# LIFT_DRIVER.net
KiCad netlist of a schematic drawn in Altium Designer
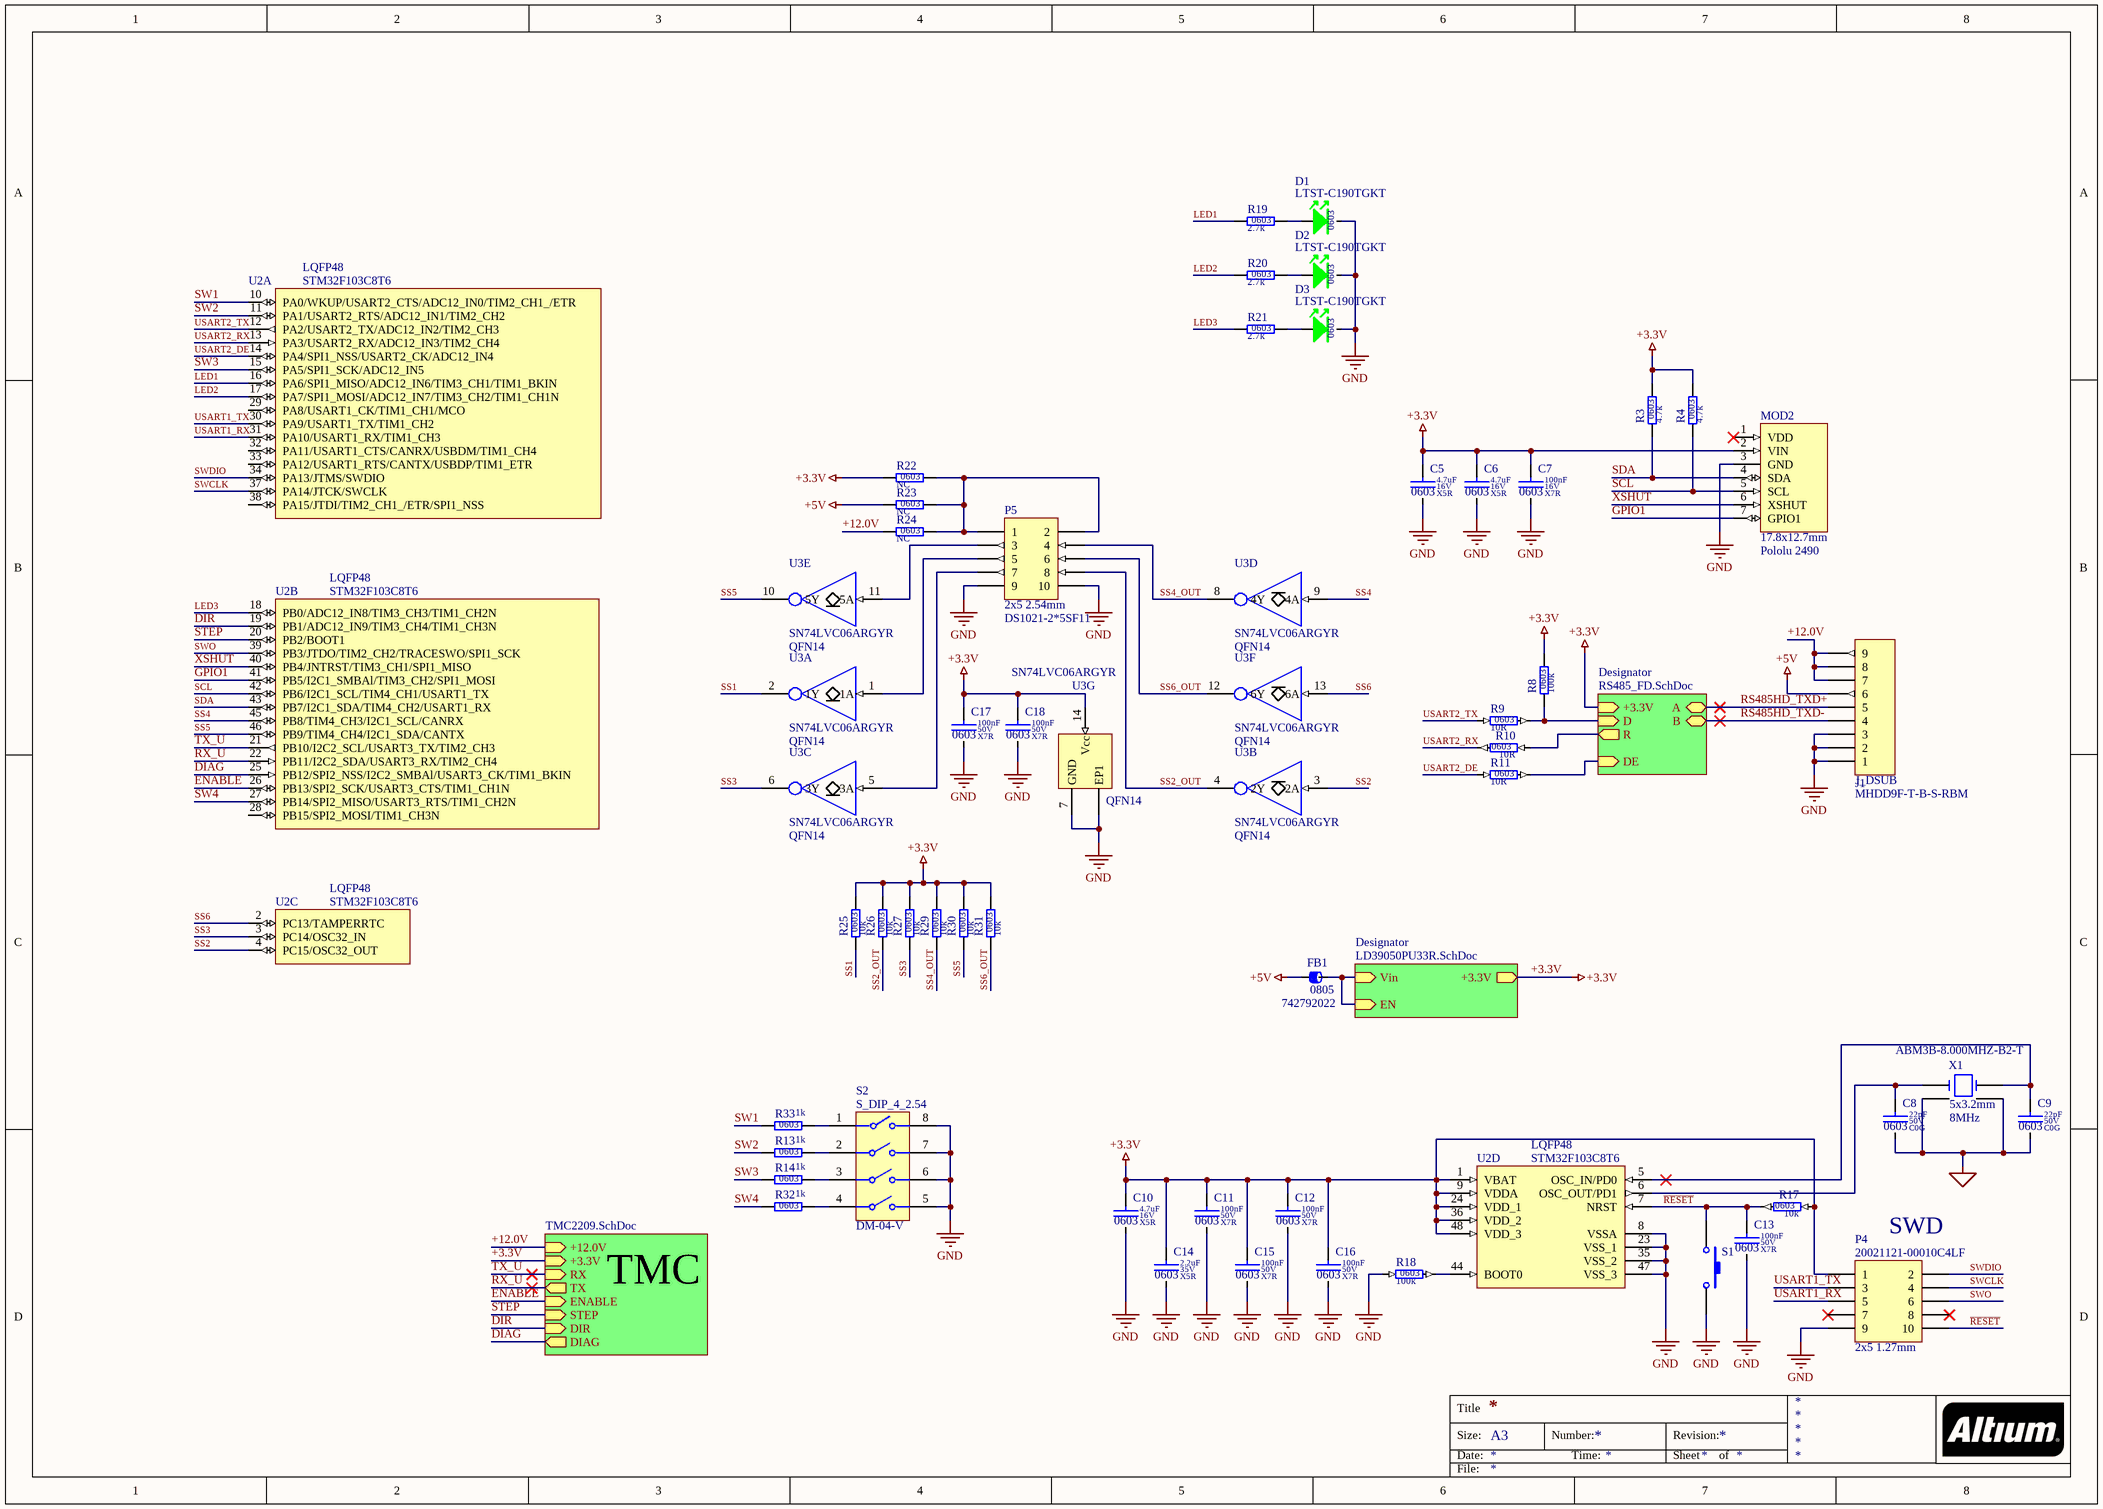
[diagram p0: LIFT_DRIVER.SchDoc]

(export (version "E")
  (design (tool "Eeschema 10.0.6"))
  (components
    (comp (ref "C5")
      (value "4.7uF")
      (footprint "C_0603_1608")
      (description "Capacitor")
      (fields
        (field (name "DIELECTRIC") "X5R")
        (field (name "VOLTAGE") "16V")
        (field (name "SCH_FOOTPRINT") "0603")
        (field (name "PART NUMBER") "C_4.7uF_16V_X5R_0603_10")
        (field (name "MANUFACTURER") "Murata")
      )
      (libsource (lib "Library") (part "C"))
    )
    (comp (ref "C6")
      (value "4.7uF")
      (footprint "C_0603_1608")
      (description "Capacitor")
      (fields
        (field (name "DIELECTRIC") "X5R")
        (field (name "VOLTAGE") "16V")
        (field (name "SCH_FOOTPRINT") "0603")
        (field (name "PART NUMBER") "C_4.7uF_16V_X5R_0603_10")
        (field (name "MANUFACTURER") "Murata")
      )
      (libsource (lib "Library") (part "C"))
    )
    (comp (ref "C7")
      (value "100nF")
      (footprint "C_0603_1608")
      (description "Capacitor")
      (fields
        (field (name "DIELECTRIC") "X7R")
        (field (name "VOLTAGE") "16V")
        (field (name "SCH_FOOTPRINT") "0603")
        (field (name "PART NUMBER") "C_100nF_16V_X7R_0603_10")
        (field (name "MANUFACTURER") "Kemet")
      )
      (libsource (lib "Library") (part "C"))
    )
    (comp (ref "C8")
      (value "22pF")
      (footprint "C_0603_1608")
      (description "Capacitor")
      (fields
        (field (name "DIELECTRIC") "C0G")
        (field (name "VOLTAGE") "50V")
        (field (name "SCH_FOOTPRINT") "0603")
        (field (name "PART NUMBER") "C_22pF_50V_C0G_0603_5")
        (field (name "MANUFACTURER") "AVX")
      )
      (libsource (lib "Library") (part "C"))
    )
    (comp (ref "C9")
      (value "22pF")
      (footprint "C_0603_1608")
      (description "Capacitor")
      (fields
        (field (name "DIELECTRIC") "C0G")
        (field (name "VOLTAGE") "50V")
        (field (name "SCH_FOOTPRINT") "0603")
        (field (name "PART NUMBER") "C_22pF_50V_C0G_0603_5")
        (field (name "MANUFACTURER") "AVX")
      )
      (libsource (lib "Library") (part "C"))
    )
    (comp (ref "C10")
      (value "4.7uF")
      (footprint "C_0603_1608")
      (description "Capacitor")
      (fields
        (field (name "DIELECTRIC") "X5R")
        (field (name "VOLTAGE") "16V")
        (field (name "SCH_FOOTPRINT") "0603")
        (field (name "PART NUMBER") "C_4.7uF_16V_X5R_0603_10")
        (field (name "MANUFACTURER") "Murata")
      )
      (libsource (lib "Library") (part "C"))
    )
    (comp (ref "C11")
      (value "100nF")
      (footprint "C_0603_1608")
      (description "Capacitor")
      (fields
        (field (name "DIELECTRIC") "X7R")
        (field (name "VOLTAGE") "50V")
        (field (name "SCH_FOOTPRINT") "0603")
        (field (name "PART NUMBER") "C_100nF_50V_X7R_0603_5")
        (field (name "MANUFACTURER") "Samsung")
      )
      (libsource (lib "Library") (part "C"))
    )
    (comp (ref "C12")
      (value "100nF")
      (footprint "C_0603_1608")
      (description "Capacitor")
      (fields
        (field (name "DIELECTRIC") "X7R")
        (field (name "VOLTAGE") "50V")
        (field (name "SCH_FOOTPRINT") "0603")
        (field (name "PART NUMBER") "C_100nF_50V_X7R_0603_5")
        (field (name "MANUFACTURER") "Samsung")
      )
      (libsource (lib "Library") (part "C"))
    )
    (comp (ref "C13")
      (value "100nF")
      (footprint "C_0603_1608")
      (description "Capacitor")
      (fields
        (field (name "DIELECTRIC") "X7R")
        (field (name "VOLTAGE") "50V")
        (field (name "SCH_FOOTPRINT") "0603")
        (field (name "PART NUMBER") "C_100nF_50V_X7R_0603_5")
        (field (name "MANUFACTURER") "Samsung")
      )
      (libsource (lib "Library") (part "C"))
    )
    (comp (ref "C14")
      (value "2.2uF")
      (footprint "C_0603_1608")
      (description "Capacitor")
      (fields
        (field (name "DIELECTRIC") "X5R")
        (field (name "VOLTAGE") "35V")
        (field (name "SCH_FOOTPRINT") "0603")
        (field (name "PART NUMBER") "C_2.2uF_35V_X5R_0603_10")
        (field (name "MANUFACTURER") "Murata")
      )
      (libsource (lib "Library") (part "C"))
    )
    (comp (ref "C15")
      (value "100nF")
      (footprint "C_0603_1608")
      (description "Capacitor")
      (fields
        (field (name "DIELECTRIC") "X7R")
        (field (name "VOLTAGE") "50V")
        (field (name "SCH_FOOTPRINT") "0603")
        (field (name "PART NUMBER") "C_100nF_50V_X7R_0603_5")
        (field (name "MANUFACTURER") "Samsung")
      )
      (libsource (lib "Library") (part "C"))
    )
    (comp (ref "C16")
      (value "100nF")
      (footprint "C_0603_1608")
      (description "Capacitor")
      (fields
        (field (name "DIELECTRIC") "X7R")
        (field (name "VOLTAGE") "50V")
        (field (name "SCH_FOOTPRINT") "0603")
        (field (name "PART NUMBER") "C_100nF_50V_X7R_0603_5")
        (field (name "MANUFACTURER") "Samsung")
      )
      (libsource (lib "Library") (part "C"))
    )
    (comp (ref "C17")
      (value "100nF")
      (footprint "C_0603_1608")
      (description "Capacitor")
      (fields
        (field (name "DIELECTRIC") "X7R")
        (field (name "VOLTAGE") "50V")
        (field (name "SCH_FOOTPRINT") "0603")
        (field (name "PART NUMBER") "C_100nF_50V_X7R_0603_5")
        (field (name "MANUFACTURER") "Samsung")
      )
      (libsource (lib "Library") (part "C"))
    )
    (comp (ref "C18")
      (value "100nF")
      (footprint "C_0603_1608")
      (description "Capacitor")
      (fields
        (field (name "DIELECTRIC") "X7R")
        (field (name "VOLTAGE") "50V")
        (field (name "SCH_FOOTPRINT") "0603")
        (field (name "PART NUMBER") "C_100nF_50V_X7R_0603_5")
        (field (name "MANUFACTURER") "Samsung")
      )
      (libsource (lib "Library") (part "C"))
    )
    (comp (ref "D1")
      (value "LTST-C190TGKT")
      (footprint "OL_0603_1608")
      (description "LED GREEN")
      (fields
        (field (name "SCH_FOOTPRINT") "0603")
        (field (name "PART NUMBER") "OL_G_0603")
        (field (name "MANUFACTURER") "Lite-On")
      )
      (libsource (lib "Library") (part "OL_G"))
    )
    (comp (ref "D2")
      (value "LTST-C190TGKT")
      (footprint "OL_0603_1608")
      (description "LED GREEN")
      (fields
        (field (name "SCH_FOOTPRINT") "0603")
        (field (name "PART NUMBER") "OL_G_0603")
        (field (name "MANUFACTURER") "Lite-On")
      )
      (libsource (lib "Library") (part "OL_G"))
    )
    (comp (ref "D3")
      (value "LTST-C190TGKT")
      (footprint "OL_0603_1608")
      (description "LED GREEN")
      (fields
        (field (name "SCH_FOOTPRINT") "0603")
        (field (name "PART NUMBER") "OL_G_0603")
        (field (name "MANUFACTURER") "Lite-On")
      )
      (libsource (lib "Library") (part "OL_G"))
    )
    (comp (ref "FB1")
      (value "742792022")
      (footprint "FB_0805_2012")
      (description "Ferrite Bead")
      (fields
        (field (name "PART NUMBER") "FB_742792022")
        (field (name "SCH_FOOTPRINT") "0805")
        (field (name "MANUFACTURER") "Wurth")
      )
      (libsource (lib "Library") (part "FB"))
    )
    (comp (ref "J1")
      (value "MHDD9F-T-B-S-RBM")
      (footprint "J_DSUB_MHDD9F-T-B-S-RBM")
      (description "Header, 9-Pin")
      (fields
        (field (name "SCH_FOOTPRINT") "J_DSUB")
        (field (name "PART NUMBER") "J_DSUB")
        (field (name "Comment") "DSUB 9 Pin")
      )
      (libsource (lib "Library") (part "J_DSUB"))
    )
    (comp (ref "MOD2")
      (value "Pololu 2490")
      (footprint "MOD_VL53L0X")
      (description "Pin Header")
      (fields
        (field (name "SCH_FOOTPRINT") "17.8x12.7mm")
        (field (name "PART NUMBER") "MOD_VL53L0X")
        (field (name "MANUFACTURER") "Polulu")
      )
      (libsource (lib "Library") (part "MOD_VL53L0X"))
    )
    (comp (ref "P4")
      (value "20021121-00010C4LF")
      (footprint "P_HEADER_2x5_1.27")
      (description "Header, 10-Pin, Dual row")
      (fields
        (field (name "PART NUMBER") "P_HEADER_2x5_1.27")
        (field (name "SCH_FOOTPRINT") "2x5 1.27mm")
        (field (name "MANUFACTURER") "FCI")
      )
      (libsource (lib "Library") (part "P_HEADER_2x5"))
    )
    (comp (ref "P5")
      (value "DS1021-2*5SF11")
      (footprint "P_HEADER_2x5_2.54")
      (description "Pin Header")
      (fields
        (field (name "SCH_FOOTPRINT") "2x5 2.54mm")
        (field (name "PART NUMBER") "P_HEADER_2x5_2.54")
        (field (name "MANUFACTURER") "Connfly")
      )
      (libsource (lib "") (part "P_HEADER_2x5_1"))
    )
    (comp (ref "R3")
      (value "4.7k")
      (footprint "R_0603_1608")
      (fields
        (field (name "SCH_FOOTPRINT") "0603")
        (field (name "PART NUMBER") "R_4.7k_0603_1")
        (field (name "VOLTAGE") "75V")
        (field (name "POWER") "100mW")
      )
      (libsource (lib "Library") (part "R"))
    )
    (comp (ref "R4")
      (value "4.7k")
      (footprint "R_0603_1608")
      (fields
        (field (name "SCH_FOOTPRINT") "0603")
        (field (name "PART NUMBER") "R_4.7k_0603_1")
        (field (name "VOLTAGE") "75V")
        (field (name "POWER") "100mW")
      )
      (libsource (lib "Library") (part "R"))
    )
    (comp (ref "R8")
      (value "100k")
      (footprint "R_0603_1608")
      (fields
        (field (name "SCH_FOOTPRINT") "0603")
        (field (name "PART NUMBER") "R_100k_0603_1")
        (field (name "VOLTAGE") "50V")
        (field (name "POWER") "100mW")
      )
      (libsource (lib "Library") (part "R"))
    )
    (comp (ref "R9")
      (value "10R")
      (footprint "R_0603_1608")
      (fields
        (field (name "SCH_FOOTPRINT") "0603")
        (field (name "PART NUMBER") "R_10R_0603_1")
        (field (name "VOLTAGE") "50V")
        (field (name "POWER") "100mW")
      )
      (libsource (lib "") (part "R_1"))
    )
    (comp (ref "R10")
      (value "10R")
      (footprint "R_0603_1608")
      (fields
        (field (name "SCH_FOOTPRINT") "0603")
        (field (name "PART NUMBER") "R_10R_0603_1")
        (field (name "VOLTAGE") "50V")
        (field (name "POWER") "100mW")
      )
      (libsource (lib "") (part "R_1"))
    )
    (comp (ref "R11")
      (value "10R")
      (footprint "R_0603_1608")
      (fields
        (field (name "SCH_FOOTPRINT") "0603")
        (field (name "PART NUMBER") "R_10R_0603_1")
        (field (name "VOLTAGE") "50V")
        (field (name "POWER") "100mW")
      )
      (libsource (lib "") (part "R_1"))
    )
    (comp (ref "R13")
      (value "1k")
      (footprint "R_0603_1608")
      (fields
        (field (name "SCH_FOOTPRINT") "0603")
        (field (name "PART NUMBER") "R_1k_0603_1")
        (field (name "VOLTAGE") "75V")
        (field (name "POWER") "100mW")
      )
      (libsource (lib "Library") (part "R"))
    )
    (comp (ref "R14")
      (value "1k")
      (footprint "R_0603_1608")
      (fields
        (field (name "SCH_FOOTPRINT") "0603")
        (field (name "PART NUMBER") "R_1k_0603_1")
        (field (name "VOLTAGE") "75V")
        (field (name "POWER") "100mW")
      )
      (libsource (lib "Library") (part "R"))
    )
    (comp (ref "R17")
      (value "10k")
      (footprint "R_0603_1608")
      (fields
        (field (name "SCH_FOOTPRINT") "0603")
        (field (name "PART NUMBER") "R_10k_0603_1")
        (field (name "VOLTAGE") "75V")
        (field (name "POWER") "100mW")
      )
      (libsource (lib "") (part "R_1"))
    )
    (comp (ref "R18")
      (value "100k")
      (footprint "R_0603_1608")
      (fields
        (field (name "SCH_FOOTPRINT") "0603")
        (field (name "PART NUMBER") "R_100k_0603_1")
        (field (name "VOLTAGE") "50V")
        (field (name "POWER") "100mW")
      )
      (libsource (lib "") (part "R_1"))
    )
    (comp (ref "R19")
      (value "2.7k")
      (footprint "R_0603_1608")
      (fields
        (field (name "SCH_FOOTPRINT") "0603")
        (field (name "PART NUMBER") "R_2.7k_0603_1")
        (field (name "VOLTAGE") "50V")
        (field (name "POWER") "100mW")
      )
      (libsource (lib "Library") (part "R"))
    )
    (comp (ref "R20")
      (value "2.7k")
      (footprint "R_0603_1608")
      (fields
        (field (name "SCH_FOOTPRINT") "0603")
        (field (name "PART NUMBER") "R_2.7k_0603_1")
        (field (name "VOLTAGE") "50V")
        (field (name "POWER") "100mW")
      )
      (libsource (lib "Library") (part "R"))
    )
    (comp (ref "R21")
      (value "2.7k")
      (footprint "R_0603_1608")
      (fields
        (field (name "SCH_FOOTPRINT") "0603")
        (field (name "PART NUMBER") "R_2.7k_0603_1")
        (field (name "VOLTAGE") "50V")
        (field (name "POWER") "100mW")
      )
      (libsource (lib "Library") (part "R"))
    )
    (comp (ref "R22")
      (value "NC")
      (footprint "R_NC_0603_1608")
      (fields
        (field (name "SCH_FOOTPRINT") "0603")
        (field (name "PART NUMBER") "R_GENERIC_0603")
        (field (name "Comment") "Resistor")
      )
      (libsource (lib "Library") (part "R"))
    )
    (comp (ref "R23")
      (value "NC")
      (footprint "R_NC_0603_1608")
      (fields
        (field (name "SCH_FOOTPRINT") "0603")
        (field (name "PART NUMBER") "R_GENERIC_0603")
        (field (name "Comment") "Resistor")
      )
      (libsource (lib "Library") (part "R"))
    )
    (comp (ref "R24")
      (value "NC")
      (footprint "R_NC_0603_1608")
      (fields
        (field (name "SCH_FOOTPRINT") "0603")
        (field (name "PART NUMBER") "R_GENERIC_0603")
        (field (name "Comment") "Resistor")
      )
      (libsource (lib "Library") (part "R"))
    )
    (comp (ref "R25")
      (value "10k")
      (footprint "R_0603_1608")
      (fields
        (field (name "SCH_FOOTPRINT") "0603")
        (field (name "PART NUMBER") "R_10k_0603_1")
        (field (name "VOLTAGE") "75V")
        (field (name "POWER") "100mW")
      )
      (libsource (lib "Library") (part "R"))
    )
    (comp (ref "R26")
      (value "10k")
      (footprint "R_0603_1608")
      (fields
        (field (name "SCH_FOOTPRINT") "0603")
        (field (name "PART NUMBER") "R_10k_0603_1")
        (field (name "VOLTAGE") "75V")
        (field (name "POWER") "100mW")
      )
      (libsource (lib "Library") (part "R"))
    )
    (comp (ref "R27")
      (value "10k")
      (footprint "R_0603_1608")
      (fields
        (field (name "SCH_FOOTPRINT") "0603")
        (field (name "PART NUMBER") "R_10k_0603_1")
        (field (name "VOLTAGE") "75V")
        (field (name "POWER") "100mW")
      )
      (libsource (lib "Library") (part "R"))
    )
    (comp (ref "R29")
      (value "10k")
      (footprint "R_0603_1608")
      (fields
        (field (name "SCH_FOOTPRINT") "0603")
        (field (name "PART NUMBER") "R_10k_0603_1")
        (field (name "VOLTAGE") "75V")
        (field (name "POWER") "100mW")
      )
      (libsource (lib "Library") (part "R"))
    )
    (comp (ref "R30")
      (value "10k")
      (footprint "R_0603_1608")
      (fields
        (field (name "SCH_FOOTPRINT") "0603")
        (field (name "PART NUMBER") "R_10k_0603_1")
        (field (name "VOLTAGE") "75V")
        (field (name "POWER") "100mW")
      )
      (libsource (lib "Library") (part "R"))
    )
    (comp (ref "R31")
      (value "10k")
      (footprint "R_0603_1608")
      (fields
        (field (name "SCH_FOOTPRINT") "0603")
        (field (name "PART NUMBER") "R_10k_0603_1")
        (field (name "VOLTAGE") "75V")
        (field (name "POWER") "100mW")
      )
      (libsource (lib "Library") (part "R"))
    )
    (comp (ref "R32")
      (value "1k")
      (footprint "R_0603_1608")
      (fields
        (field (name "SCH_FOOTPRINT") "0603")
        (field (name "PART NUMBER") "R_1k_0603_1")
        (field (name "VOLTAGE") "75V")
        (field (name "POWER") "100mW")
      )
      (libsource (lib "Library") (part "R"))
    )
    (comp (ref "R33")
      (value "1k")
      (footprint "R_0603_1608")
      (fields
        (field (name "SCH_FOOTPRINT") "0603")
        (field (name "PART NUMBER") "R_1k_0603_1")
        (field (name "VOLTAGE") "75V")
        (field (name "POWER") "100mW")
      )
      (libsource (lib "Library") (part "R"))
    )
    (comp (ref "S1")
      (value "3x6mm")
      (footprint "S_TACTSWITCH3x6")
      (description "Tact Switch")
      (fields (field (name "PART NUMBER") "S_TACTSWITCH") (field (name "MANUFACTURER") "Ninigi"))
      (libsource (lib "Library") (part "S_TACTSWITCH"))
    )
    (comp (ref "S2")
      (value "DM-04-V")
      (footprint "DM-04-V")
      (fields
        (field (name "SCH_FOOTPRINT") "S_DIP_4_2.54")
        (field (name "PART NUMBER") "S_DM-04-V")
        (field (name "MANUFACTURER") "DIPTRONICS")
        (field (name "Comment") "DIP SWITCH 4 POS")
      )
      (libsource (lib "Library") (part "S_DIP_SWITCH_4"))
    )
    (comp (ref "U2")
      (value "STM32F103C8T6")
      (footprint "LQFP48_7x7")
      (fields
        (field (name "SCH_FOOTPRINT") "LQFP48")
        (field (name "PART NUMBER") "UP_STM32F103C8T6")
        (field (name "MANUFACTURER") "STMicroelectronics")
      )
      (libsource (lib "Library") (part "UP_STM32F103Cx"))
    )
    (comp (ref "U3")
      (value "SN74LVC06ARGYR")
      (footprint "QFN14_4x4")
      (fields
        (field (name "PART NUMBER") "U_SN74LVC06ARGYR")
        (field (name "SCH_FOOTPRINT") "QFN14")
        (field (name "MANUFACTURER") "Texas Instruments")
        (field (name "Comment") "Open drain buffer")
      )
      (libsource (lib "Library") (part "U_SN74LVC06A"))
    )
    (comp (ref "X1")
      (value "8MHz")
      (footprint "X_ABM3B_5X3X11")
      (fields
        (field (name "PART NUMBER") "X_ABM3B-8.000MHZ-B2-T")
        (field (name "MANUFACTURER PART NUMBER") "ABM3B-8.000MHZ-B2-T")
        (field (name "SCH_FOOTPRINT") "5x3.2mm")
        (field (name "MANUFACTURER") "Abracon")
      )
      (libsource (lib "Library") (part "X_ABM3B"))
    )
  )
  (nets
    (net (code "1") (name "+3.3V") (class "Default")
      (node (ref "C10") (pin "1") (pinfunction "1_1") (pintype "passive"))
      (node (ref "C11") (pin "1") (pinfunction "1_1") (pintype "passive"))
      (node (ref "C12") (pin "1") (pinfunction "1_1") (pintype "passive"))
      (node (ref "C14") (pin "1") (pinfunction "1_1") (pintype "passive"))
      (node (ref "C15") (pin "1") (pinfunction "1_1") (pintype "passive"))
      (node (ref "C16") (pin "1") (pinfunction "1_1") (pintype "passive"))
      (node (ref "C17") (pin "1") (pinfunction "1_1") (pintype "passive"))
      (node (ref "C18") (pin "1") (pinfunction "1_1") (pintype "passive"))
      (node (ref "C5") (pin "1") (pinfunction "1_1") (pintype "passive"))
      (node (ref "C6") (pin "1") (pinfunction "1_1") (pintype "passive"))
      (node (ref "C7") (pin "1") (pinfunction "1_1") (pintype "passive"))
      (node (ref "MOD2") (pin "2") (pinfunction "VIN_2") (pintype "input"))
      (node (ref "P4") (pin "1") (pinfunction "1_1") (pintype "passive"))
      (node (ref "R17") (pin "1") (pinfunction "1_1") (pintype "input"))
      (node (ref "R22") (pin "1") (pinfunction "1_1") (pintype "passive"))
      (node (ref "R25") (pin "2") (pinfunction "2_2") (pintype "passive"))
      (node (ref "R26") (pin "2") (pinfunction "2_2") (pintype "passive"))
      (node (ref "R27") (pin "2") (pinfunction "2_2") (pintype "passive"))
      (node (ref "R29") (pin "2") (pinfunction "2_2") (pintype "passive"))
      (node (ref "R3") (pin "2") (pinfunction "2_2") (pintype "passive"))
      (node (ref "R30") (pin "2") (pinfunction "2_2") (pintype "passive"))
      (node (ref "R31") (pin "2") (pinfunction "2_2") (pintype "passive"))
      (node (ref "R4") (pin "2") (pinfunction "2_2") (pintype "passive"))
      (node (ref "R8") (pin "2") (pinfunction "2_2") (pintype "passive"))
      (node (ref "U2") (pin "1") (pinfunction "VBAT_1") (pintype "input"))
      (node (ref "U2") (pin "24") (pinfunction "VDD_1_24") (pintype "input"))
      (node (ref "U2") (pin "36") (pinfunction "VDD_2_36") (pintype "input"))
      (node (ref "U2") (pin "48") (pinfunction "VDD_3_48") (pintype "input"))
      (node (ref "U2") (pin "9") (pinfunction "VDDA_9") (pintype "input"))
      (node (ref "U3") (pin "14") (pinfunction "Vcc_14") (pintype "input"))
    )
    (net (code "2") (name "+5V") (class "Default")
      (node (ref "FB1") (pin "1") (pintype "input"))
      (node (ref "J1") (pin "6") (pinfunction "6_6") (pintype "output"))
      (node (ref "R23") (pin "1") (pinfunction "1_1") (pintype "passive"))
    )
    (net (code "3") (name "/+12.0V") (class "Default")
      (node (ref "J1") (pin "7") (pinfunction "7_7") (pintype "passive"))
      (node (ref "J1") (pin "8") (pinfunction "8_8") (pintype "passive"))
      (node (ref "J1") (pin "9") (pinfunction "9_9") (pintype "output"))
      (node (ref "R24") (pin "1") (pinfunction "1_1") (pintype "passive"))
    )
    (net (code "4") (name "/D") (class "Default")
      (node (ref "R8") (pin "1") (pinfunction "1_1") (pintype "passive"))
      (node (ref "R9") (pin "2") (pinfunction "2_2") (pintype "output"))
    )
    (net (code "5") (name "/DE") (class "Default")
      (node (ref "R11") (pin "2") (pinfunction "2_2") (pintype "output"))
    )
    (net (code "6") (name "/DIAG") (class "Default")
      (node (ref "U2") (pin "25") (pinfunction "PB12/SPI2_NSS/I2C2_SMBAl/USART3_CK/TIM1_BKIN_25") (pintype "bidirectional"))
    )
    (net (code "7") (name "/DIR") (class "Default")
      (node (ref "U2") (pin "19") (pinfunction "PB1/ADC12_IN9/TIM3_CH4/TIM1_CH3N_19") (pintype "bidirectional"))
    )
    (net (code "8") (name "/EN") (class "Default") (node (ref "FB1") (pin "2") (pintype "output")))
    (net (code "9") (name "/ENABLE") (class "Default")
      (node (ref "U2") (pin "26") (pinfunction "PB13/SPI2_SCK/USART3_CTS/TIM1_CH1N_26") (pintype "bidirectional"))
    )
    (net (code "10") (name "/GPIO1") (class "Default")
      (node (ref "MOD2") (pin "7") (pinfunction "GPIO1_7") (pintype "bidirectional"))
      (node (ref "U2") (pin "41") (pinfunction "PB5/I2C1_SMBAl/TIM3_CH2/SPI1_MOSI_41") (pintype "bidirectional"))
    )
    (net (code "11") (name "/LED1") (class "Default")
      (node (ref "R19") (pin "1") (pinfunction "1_1") (pintype "passive"))
      (node (ref "U2") (pin "16") (pinfunction "PA6/SPI1_MISO/ADC12_IN6/TIM3_CH1/TIM1_BKIN_16") (pintype "bidirectional"))
    )
    (net (code "12") (name "/LED2") (class "Default")
      (node (ref "R20") (pin "1") (pinfunction "1_1") (pintype "passive"))
      (node (ref "U2") (pin "17") (pinfunction "PA7/SPI1_MOSI/ADC12_IN7/TIM3_CH2/TIM1_CH1N_17") (pintype "bidirectional"))
    )
    (net (code "13") (name "/LED3") (class "Default")
      (node (ref "R21") (pin "1") (pinfunction "1_1") (pintype "passive"))
      (node (ref "U2") (pin "18") (pinfunction "PB0/ADC12_IN8/TIM3_CH3/TIM1_CH2N_18") (pintype "bidirectional"))
    )
    (net (code "14") (name "/R") (class "Default")
      (node (ref "R10") (pin "1") (pinfunction "1_1") (pintype "input"))
    )
    (net (code "15") (name "/RS485HD_TXD+") (class "Default")
      (node (ref "J1") (pin "5") (pinfunction "5_5") (pintype "passive"))
    )
    (net (code "16") (name "/RS485HD_TXD-") (class "Default")
      (node (ref "J1") (pin "4") (pinfunction "4_4") (pintype "passive"))
    )
    (net (code "17") (name "/RX_U") (class "Default")
      (node (ref "U2") (pin "22") (pinfunction "PB11/I2C2_SDA/USART3_RX/TIM2_CH4_22") (pintype "bidirectional"))
    )
    (net (code "18") (name "/SCL") (class "Default")
      (node (ref "MOD2") (pin "5") (pinfunction "SCL_5") (pintype "input"))
      (node (ref "R4") (pin "1") (pinfunction "1_1") (pintype "passive"))
      (node (ref "U2") (pin "42") (pinfunction "PB6/I2C1_SCL/TIM4_CH1/USART1_TX_42") (pintype "bidirectional"))
    )
    (net (code "19") (name "/SDA") (class "Default")
      (node (ref "MOD2") (pin "4") (pinfunction "SDA_4") (pintype "bidirectional"))
      (node (ref "R3") (pin "1") (pinfunction "1_1") (pintype "passive"))
      (node (ref "U2") (pin "43") (pinfunction "PB7/I2C1_SDA/TIM4_CH2/USART1_RX_43") (pintype "bidirectional"))
    )
    (net (code "20") (name "/SS1") (class "Default")
      (node (ref "R25") (pin "1") (pinfunction "1_1") (pintype "passive"))
      (node (ref "U3") (pin "2") (pinfunction "1Y_2") (pintype "open_collector"))
    )
    (net (code "21") (name "/SS2") (class "Default")
      (node (ref "U2") (pin "4") (pinfunction "PC15/OSC32_OUT_4") (pintype "bidirectional"))
      (node (ref "U3") (pin "3") (pinfunction "2A_3") (pintype "input"))
    )
    (net (code "22") (name "/SS2_OUT") (class "Default")
      (node (ref "P5") (pin "8") (pinfunction "8_8") (pintype "input"))
      (node (ref "R26") (pin "1") (pinfunction "1_1") (pintype "passive"))
      (node (ref "U3") (pin "4") (pinfunction "2Y_4") (pintype "open_collector"))
    )
    (net (code "23") (name "/SS3") (class "Default")
      (node (ref "R27") (pin "1") (pinfunction "1_1") (pintype "passive"))
      (node (ref "U2") (pin "3") (pinfunction "PC14/OSC32_IN_3") (pintype "bidirectional"))
      (node (ref "U3") (pin "6") (pinfunction "3Y_6") (pintype "open_collector"))
    )
    (net (code "24") (name "/SS4") (class "Default")
      (node (ref "U2") (pin "45") (pinfunction "PB8/TIM4_CH3/I2C1_SCL/CANRX_45") (pintype "bidirectional"))
      (node (ref "U3") (pin "9") (pinfunction "4A_9") (pintype "input"))
    )
    (net (code "25") (name "/SS4_OUT") (class "Default")
      (node (ref "P5") (pin "4") (pinfunction "4_4") (pintype "input"))
      (node (ref "R29") (pin "1") (pinfunction "1_1") (pintype "passive"))
      (node (ref "U3") (pin "8") (pinfunction "4Y_8") (pintype "open_collector"))
    )
    (net (code "26") (name "/SS5") (class "Default")
      (node (ref "R30") (pin "1") (pinfunction "1_1") (pintype "passive"))
      (node (ref "U2") (pin "46") (pinfunction "PB9/TIM4_CH4/I2C1_SDA/CANTX_46") (pintype "bidirectional"))
      (node (ref "U3") (pin "10") (pinfunction "5Y_10") (pintype "open_collector"))
    )
    (net (code "27") (name "/SS6") (class "Default")
      (node (ref "U2") (pin "2") (pinfunction "PC13/TAMPERRTC_2") (pintype "bidirectional"))
      (node (ref "U3") (pin "13") (pinfunction "6A_13") (pintype "input"))
    )
    (net (code "28") (name "/SS6_OUT") (class "Default")
      (node (ref "P5") (pin "6") (pinfunction "6_6") (pintype "input"))
      (node (ref "R31") (pin "1") (pinfunction "1_1") (pintype "passive"))
      (node (ref "U3") (pin "12") (pinfunction "6Y_12") (pintype "open_collector"))
    )
    (net (code "29") (name "/STEP") (class "Default")
      (node (ref "U2") (pin "20") (pinfunction "PB2/BOOT1_20") (pintype "bidirectional"))
    )
    (net (code "30") (name "/SW1") (class "Default")
      (node (ref "R33") (pin "1") (pinfunction "1_1") (pintype "passive"))
      (node (ref "U2") (pin "10") (pinfunction "PA0/WKUP/USART2_CTS/ADC12_IN0/TIM2_CH1_/ETR_10") (pintype "bidirectional"))
    )
    (net (code "31") (name "/SW2") (class "Default")
      (node (ref "R13") (pin "1") (pinfunction "1_1") (pintype "passive"))
      (node (ref "U2") (pin "11") (pinfunction "PA1/USART2_RTS/ADC12_IN1/TIM2_CH2_11") (pintype "bidirectional"))
    )
    (net (code "32") (name "/SW3") (class "Default")
      (node (ref "R14") (pin "1") (pinfunction "1_1") (pintype "passive"))
      (node (ref "U2") (pin "15") (pinfunction "PA5/SPI1_SCK/ADC12_IN5_15") (pintype "bidirectional"))
    )
    (net (code "33") (name "/SW4") (class "Default")
      (node (ref "R32") (pin "1") (pinfunction "1_1") (pintype "passive"))
      (node (ref "U2") (pin "27") (pinfunction "PB14/SPI2_MISO/USART3_RTS/TIM1_CH2N_27") (pintype "bidirectional"))
    )
    (net (code "34") (name "/SWCLK") (class "Default")
      (node (ref "P4") (pin "4") (pinfunction "4_4") (pintype "passive"))
      (node (ref "U2") (pin "37") (pinfunction "PA14/JTCK/SWCLK_37") (pintype "bidirectional"))
    )
    (net (code "35") (name "/SWDIO") (class "Default")
      (node (ref "P4") (pin "2") (pinfunction "2_2") (pintype "passive"))
      (node (ref "U2") (pin "34") (pinfunction "PA13/JTMS/SWDIO_34") (pintype "bidirectional"))
    )
    (net (code "36") (name "/SWO") (class "Default")
      (node (ref "P4") (pin "6") (pinfunction "6_6") (pintype "passive"))
      (node (ref "U2") (pin "39") (pinfunction "PB3/JTDO/TIM2_CH2/TRACESWO/SPI1_SCK_39") (pintype "bidirectional"))
    )
    (net (code "37") (name "/TX_U") (class "Default")
      (node (ref "U2") (pin "21") (pinfunction "PB10/I2C2_SCL/USART3_TX/TIM2_CH3_21") (pintype "bidirectional"))
    )
    (net (code "38") (name "/USART1_RX") (class "Default")
      (node (ref "P4") (pin "5") (pinfunction "5_5") (pintype "passive"))
      (node (ref "U2") (pin "31") (pinfunction "PA10/USART1_RX/TIM1_CH3_31") (pintype "bidirectional"))
    )
    (net (code "39") (name "/USART1_TX") (class "Default")
      (node (ref "P4") (pin "3") (pinfunction "3_3") (pintype "passive"))
      (node (ref "U2") (pin "30") (pinfunction "PA9/USART1_TX/TIM1_CH2_30") (pintype "bidirectional"))
    )
    (net (code "40") (name "/USART2_DE") (class "Default")
      (node (ref "R11") (pin "1") (pinfunction "1_1") (pintype "input"))
      (node (ref "U2") (pin "14") (pinfunction "PA4/SPI1_NSS/USART2_CK/ADC12_IN4_14") (pintype "bidirectional"))
    )
    (net (code "41") (name "/USART2_RX") (class "Default")
      (node (ref "R10") (pin "2") (pinfunction "2_2") (pintype "output"))
      (node (ref "U2") (pin "13") (pinfunction "PA3/USART2_RX/ADC12_IN3/TIM2_CH4_13") (pintype "input"))
    )
    (net (code "42") (name "/USART2_TX") (class "Default")
      (node (ref "R9") (pin "1") (pinfunction "1_1") (pintype "input"))
      (node (ref "U2") (pin "12") (pinfunction "PA2/USART2_TX/ADC12_IN2/TIM2_CH3_12") (pintype "output"))
    )
    (net (code "43") (name "/XSHUT") (class "Default")
      (node (ref "MOD2") (pin "6") (pinfunction "XSHUT_6") (pintype "input"))
      (node (ref "U2") (pin "40") (pinfunction "PB4/JNTRST/TIM3_CH1/SPI1_MISO_40") (pintype "bidirectional"))
    )
    (net (code "44") (name "/~{RESET}") (class "Default")
      (node (ref "C13") (pin "1") (pinfunction "1_1") (pintype "passive"))
      (node (ref "P4") (pin "10") (pinfunction "10_10") (pintype "passive"))
      (node (ref "R17") (pin "2") (pinfunction "2_2") (pintype "output"))
      (node (ref "S1") (pin "1") (pinfunction "1_1") (pintype "passive"))
      (node (ref "U2") (pin "7") (pinfunction "NRST_7") (pintype "input"))
    )
    (net (code "45") (name "GND") (class "Default")
      (node (ref "C10") (pin "2") (pinfunction "2_2") (pintype "passive"))
      (node (ref "C11") (pin "2") (pinfunction "2_2") (pintype "passive"))
      (node (ref "C12") (pin "2") (pinfunction "2_2") (pintype "passive"))
      (node (ref "C13") (pin "2") (pinfunction "2_2") (pintype "passive"))
      (node (ref "C14") (pin "2") (pinfunction "2_2") (pintype "passive"))
      (node (ref "C15") (pin "2") (pinfunction "2_2") (pintype "passive"))
      (node (ref "C16") (pin "2") (pinfunction "2_2") (pintype "passive"))
      (node (ref "C17") (pin "2") (pinfunction "2_2") (pintype "passive"))
      (node (ref "C18") (pin "2") (pinfunction "2_2") (pintype "passive"))
      (node (ref "C5") (pin "2") (pinfunction "2_2") (pintype "passive"))
      (node (ref "C6") (pin "2") (pinfunction "2_2") (pintype "passive"))
      (node (ref "C7") (pin "2") (pinfunction "2_2") (pintype "passive"))
      (node (ref "C8") (pin "2") (pinfunction "2_2") (pintype "passive"))
      (node (ref "C9") (pin "2") (pinfunction "2_2") (pintype "passive"))
      (node (ref "D1") (pin "1") (pinfunction "K_1") (pintype "passive"))
      (node (ref "D2") (pin "1") (pinfunction "K_1") (pintype "passive"))
      (node (ref "D3") (pin "1") (pinfunction "K_1") (pintype "passive"))
      (node (ref "J1") (pin "1") (pinfunction "1_1") (pintype "passive"))
      (node (ref "J1") (pin "2") (pinfunction "2_2") (pintype "passive"))
      (node (ref "J1") (pin "3") (pinfunction "3_3") (pintype "passive"))
      (node (ref "MOD2") (pin "3") (pinfunction "GND_3") (pintype "power_in"))
      (node (ref "P4") (pin "9") (pinfunction "9_9") (pintype "passive"))
      (node (ref "P5") (pin "10") (pinfunction "10_10") (pintype "passive"))
      (node (ref "P5") (pin "9") (pinfunction "9_9") (pintype "passive"))
      (node (ref "R18") (pin "1") (pinfunction "1_1") (pintype "input"))
      (node (ref "S1") (pin "2") (pinfunction "2_2") (pintype "passive"))
      (node (ref "S2") (pin "5") (pinfunction "5_5") (pintype "passive"))
      (node (ref "S2") (pin "6") (pinfunction "6_6") (pintype "passive"))
      (node (ref "S2") (pin "7") (pinfunction "7_7") (pintype "passive"))
      (node (ref "S2") (pin "8") (pinfunction "8_8") (pintype "passive"))
      (node (ref "U2") (pin "23") (pinfunction "VSS_1_23") (pintype "power_in"))
      (node (ref "U2") (pin "35") (pinfunction "VSS_2_35") (pintype "power_in"))
      (node (ref "U2") (pin "47") (pinfunction "VSS_3_47") (pintype "power_in"))
      (node (ref "U2") (pin "8") (pinfunction "VSSA_8") (pintype "power_in"))
      (node (ref "U3") (pin "7") (pinfunction "GND_7") (pintype "power_in"))
      (node (ref "U3") (pin "EP1") (pinfunction "EP1_EP1") (pintype "power_in"))
      (node (ref "X1") (pin "2") (pinfunction "GND_2") (pintype "power_in"))
      (node (ref "X1") (pin "4") (pinfunction "GND_4") (pintype "power_in"))
    )
    (net (code "46") (name "Net-(D1-A)") (class "Default")
      (node (ref "D1") (pin "2") (pinfunction "A_2") (pintype "passive"))
      (node (ref "R19") (pin "2") (pinfunction "2_2") (pintype "passive"))
    )
    (net (code "47") (name "Net-(D2-A)") (class "Default")
      (node (ref "D2") (pin "2") (pinfunction "A_2") (pintype "passive"))
      (node (ref "R20") (pin "2") (pinfunction "2_2") (pintype "passive"))
    )
    (net (code "48") (name "Net-(D3-A)") (class "Default")
      (node (ref "D3") (pin "2") (pinfunction "A_2") (pintype "passive"))
      (node (ref "R21") (pin "2") (pinfunction "2_2") (pintype "passive"))
    )
    (net (code "49") (name "Net-(P5-Pad1)") (class "Default")
      (node (ref "P5") (pin "1") (pinfunction "1_1") (pintype "passive"))
      (node (ref "P5") (pin "2") (pinfunction "2_2") (pintype "passive"))
      (node (ref "R22") (pin "2") (pinfunction "2_2") (pintype "passive"))
      (node (ref "R23") (pin "2") (pinfunction "2_2") (pintype "passive"))
      (node (ref "R24") (pin "2") (pinfunction "2_2") (pintype "passive"))
    )
    (net (code "50") (name "Net-(R13-Pad2)") (class "Default")
      (node (ref "R13") (pin "2") (pinfunction "2_2") (pintype "passive"))
      (node (ref "S2") (pin "2") (pinfunction "2_2") (pintype "passive"))
    )
    (net (code "51") (name "Net-(R14-Pad2)") (class "Default")
      (node (ref "R14") (pin "2") (pinfunction "2_2") (pintype "passive"))
      (node (ref "S2") (pin "3") (pinfunction "3_3") (pintype "passive"))
    )
    (net (code "52") (name "Net-(R32-Pad2)") (class "Default")
      (node (ref "R32") (pin "2") (pinfunction "2_2") (pintype "passive"))
      (node (ref "S2") (pin "4") (pinfunction "4_4") (pintype "passive"))
    )
    (net (code "53") (name "Net-(R33-Pad2)") (class "Default")
      (node (ref "R33") (pin "2") (pinfunction "2_2") (pintype "passive"))
      (node (ref "S2") (pin "1") (pinfunction "1_1") (pintype "passive"))
    )
    (net (code "54") (name "Net-(U2D-BOOT0)") (class "Default")
      (node (ref "R18") (pin "2") (pinfunction "2_2") (pintype "output"))
      (node (ref "U2") (pin "44") (pinfunction "BOOT0_44") (pintype "input"))
    )
    (net (code "55") (name "Net-(U2D-OSC_IN{slash}PD0)") (class "Default")
      (node (ref "C9") (pin "1") (pinfunction "1_1") (pintype "passive"))
      (node (ref "U2") (pin "5") (pinfunction "OSC_IN/PD0_5") (pintype "input"))
      (node (ref "X1") (pin "1") (pinfunction "1_1") (pintype "passive"))
    )
    (net (code "56") (name "Net-(U2D-OSC_OUT{slash}PD1)") (class "Default")
      (node (ref "C8") (pin "1") (pinfunction "1_1") (pintype "passive"))
      (node (ref "U2") (pin "6") (pinfunction "OSC_OUT/PD1_6") (pintype "output"))
      (node (ref "X1") (pin "3") (pinfunction "3_3") (pintype "passive"))
    )
    (net (code "57") (name "Net-(U3A-1A)") (class "Default")
      (node (ref "P5") (pin "5") (pinfunction "5_5") (pintype "output"))
      (node (ref "U3") (pin "1") (pinfunction "1A_1") (pintype "input"))
    )
    (net (code "58") (name "Net-(U3C-3A)") (class "Default")
      (node (ref "P5") (pin "7") (pinfunction "7_7") (pintype "output"))
      (node (ref "U3") (pin "5") (pinfunction "3A_5") (pintype "input"))
    )
    (net (code "59") (name "Net-(U3E-5A)") (class "Default")
      (node (ref "P5") (pin "3") (pinfunction "3_3") (pintype "output"))
      (node (ref "U3") (pin "11") (pinfunction "5A_11") (pintype "input"))
    )
    (net (code "60") (name "unconnected-(J1-NC-Pad0)") (class "Default")
      (node (ref "J1") (pin "0") (pinfunction "NC_0") (pintype "passive"))
    )
    (net (code "61") (name "unconnected-(MOD2-VDD-Pad1)") (class "Default")
      (node (ref "MOD2") (pin "1") (pinfunction "VDD_1") (pintype "input+no_connect"))
    )
    (net (code "62") (name "unconnected-(P4-Pad7)") (class "Default")
      (node (ref "P4") (pin "7") (pinfunction "7_7") (pintype "passive+no_connect"))
    )
    (net (code "63") (name "unconnected-(P4-Pad8)") (class "Default")
      (node (ref "P4") (pin "8") (pinfunction "8_8") (pintype "passive+no_connect"))
    )
    (net (code "64") (name "unconnected-(U2A-PA8{slash}USART1_CK{slash}TIM1_CH1{slash}MCO-Pad29)") (class "Default")
      (node (ref "U2") (pin "29") (pinfunction "PA8/USART1_CK/TIM1_CH1/MCO_29") (pintype "bidirectional"))
    )
    (net (code "65") (name "unconnected-(U2A-PA11{slash}USART1_CTS{slash}CANRX{slash}USBDM{slash}TIM1_CH4-Pad32)") (class "Default")
      (node (ref "U2") (pin "32") (pinfunction "PA11/USART1_CTS/CANRX/USBDM/TIM1_CH4_32") (pintype "bidirectional"))
    )
    (net (code "66") (name "unconnected-(U2A-PA12{slash}USART1_RTS{slash}CANTX{slash}USBDP{slash}TIM1_ETR-Pad33)") (class "Default")
      (node (ref "U2") (pin "33") (pinfunction "PA12/USART1_RTS/CANTX/USBDP/TIM1_ETR_33") (pintype "bidirectional"))
    )
    (net (code "67") (name "unconnected-(U2A-PA15{slash}JTDI{slash}TIM2_CH1_{slash}ETR{slash}SPI1_NSS-Pad38)") (class "Default")
      (node (ref "U2") (pin "38") (pinfunction "PA15/JTDI/TIM2_CH1_/ETR/SPI1_NSS_38") (pintype "bidirectional"))
    )
    (net (code "68") (name "unconnected-(U2B-PB15{slash}SPI2_MOSI{slash}TIM1_CH3N-Pad28)") (class "Default")
      (node (ref "U2") (pin "28") (pinfunction "PB15/SPI2_MOSI/TIM1_CH3N_28") (pintype "bidirectional"))
    )
  )
)
